# Heaters.net
KiCad netlist of a schematic drawn in Altium Designer
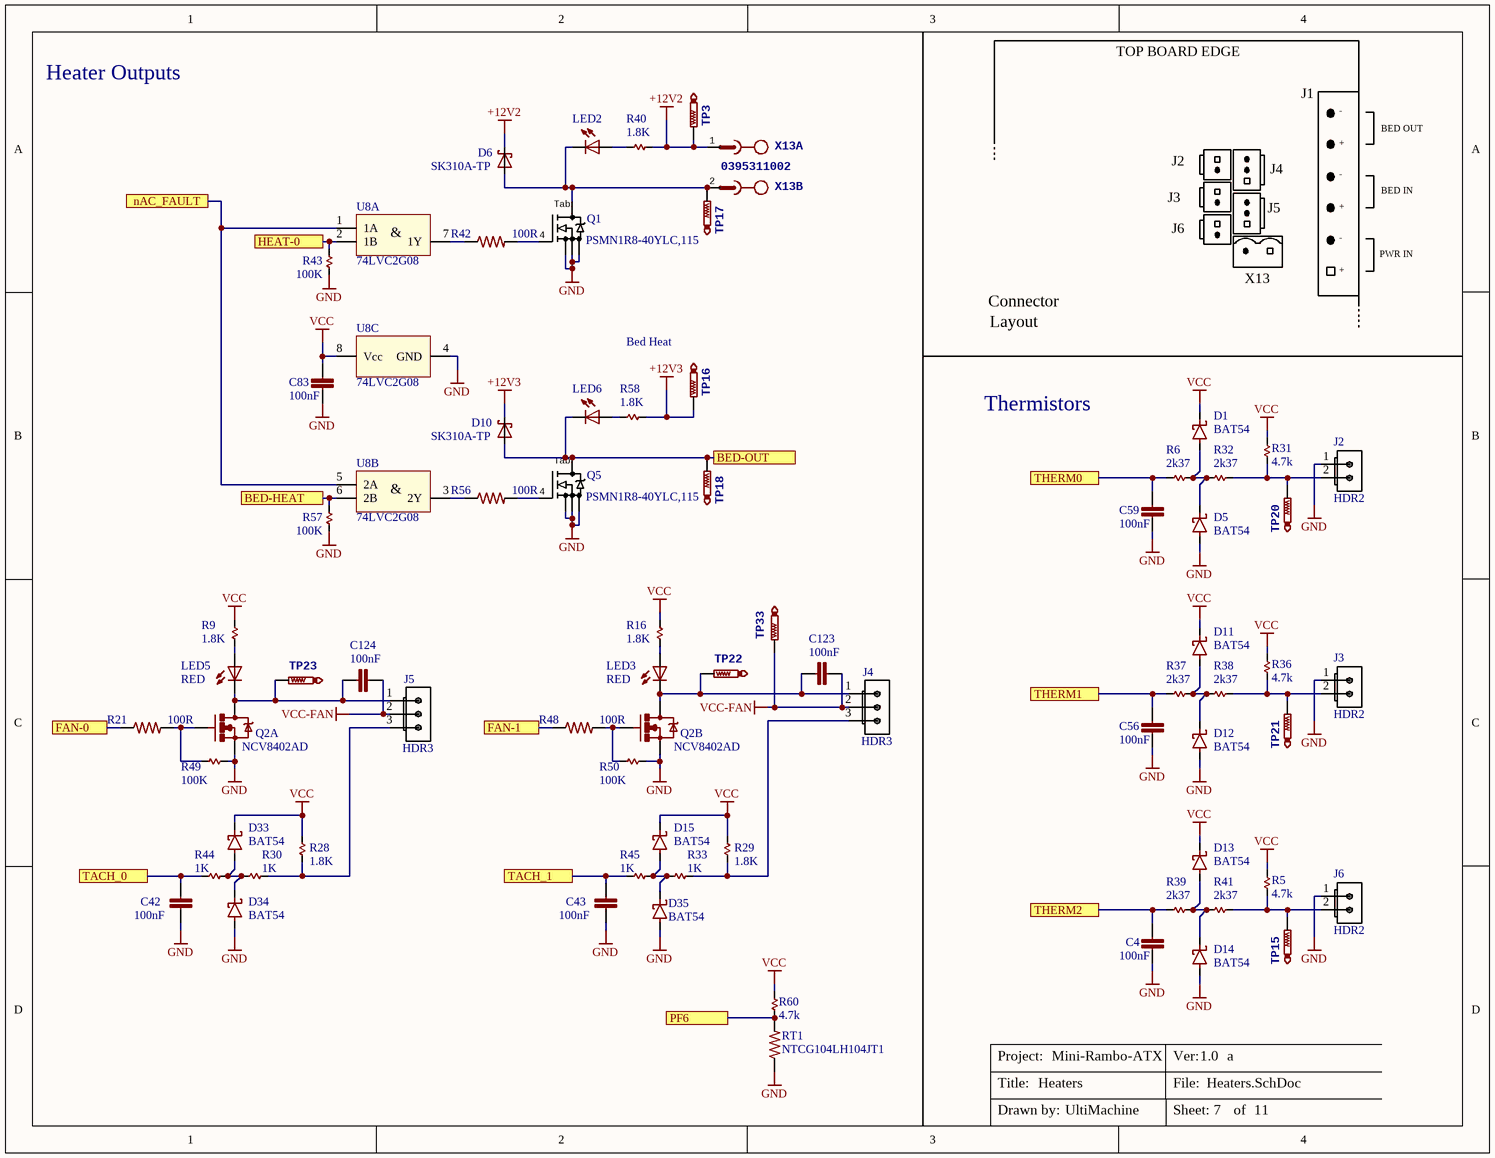
[diagram p0: Heaters.SchDoc]

(export (version "E")
  (design (tool "Eeschema 10.0.6"))
  (components
    (comp (ref "C4")
      (value "100nF")
      (footprint "C0402")
      (description "CAP CER 0402 100nF 16V 10% X7R")
      (fields (field (name "MANUFACTURER") "Murata") (field (name "TOLERANCE") "+/- 10%"))
      (libsource (lib "3Delight") (part "GRM155R71C104KA88D"))
    )
    (comp (ref "C42")
      (value "100nF")
      (footprint "C0402")
      (description "CAP CER 0402 100nF 16V 10% X7R")
      (fields (field (name "MANUFACTURER") "Murata") (field (name "TOLERANCE") "+/- 10%"))
      (libsource (lib "3Delight") (part "GRM155R71C104KA88D"))
    )
    (comp (ref "C43")
      (value "100nF")
      (footprint "C0402")
      (description "CAP CER 0402 100nF 16V 10% X7R")
      (fields (field (name "MANUFACTURER") "Murata") (field (name "TOLERANCE") "+/- 10%"))
      (libsource (lib "3Delight") (part "GRM155R71C104KA88D"))
    )
    (comp (ref "C56")
      (value "100nF")
      (footprint "C0402")
      (description "CAP CER 0402 100nF 16V 10% X7R")
      (fields (field (name "MANUFACTURER") "Murata") (field (name "TOLERANCE") "+/- 10%"))
      (libsource (lib "3Delight") (part "GRM155R71C104KA88D"))
    )
    (comp (ref "C59")
      (value "100nF")
      (footprint "C0402")
      (description "CAP CER 0402 100nF 16V 10% X7R")
      (fields (field (name "MANUFACTURER") "Murata") (field (name "TOLERANCE") "+/- 10%"))
      (libsource (lib "3Delight") (part "GRM155R71C104KA88D"))
    )
    (comp (ref "C83")
      (value "100nF")
      (footprint "C0402")
      (description "CAP CER 0402 100nF 16V 10% X7R")
      (fields (field (name "MANUFACTURER") "Murata") (field (name "TOLERANCE") "+/- 10%"))
      (libsource (lib "3Delight") (part "GRM155R71C104KA88D"))
    )
    (comp (ref "C123")
      (value "100nF")
      (footprint "C0402")
      (description "CAP CER 0402 100nF 16V 10% X7R")
      (fields (field (name "MANUFACTURER") "Murata") (field (name "TOLERANCE") "+/- 10%"))
      (libsource (lib "") (part "GRM155R71C104KA88D_1"))
    )
    (comp (ref "C124")
      (value "100nF")
      (footprint "C0402")
      (description "CAP CER 0402 100nF 16V 10% X7R")
      (fields (field (name "MANUFACTURER") "Murata") (field (name "TOLERANCE") "+/- 10%"))
      (libsource (lib "") (part "GRM155R71C104KA88D_1"))
    )
    (comp (ref "D1")
      (value "BAT54")
      (footprint "SOD523_IPC")
      (description "Diode Schottky 30V 100mA Surface Mount SOD-523")
      (fields (field (name "MANUFACTURER") "Diodes Incorporated") (field (name "TOLERANCE") "NA"))
      (libsource (lib "3Delight") (part "BAT54WT-7"))
    )
    (comp (ref "D5")
      (value "BAT54")
      (footprint "SOD523_IPC")
      (description "Diode Schottky 30V 100mA Surface Mount SOD-523")
      (fields (field (name "MANUFACTURER") "Diodes Incorporated") (field (name "TOLERANCE") "NA"))
      (libsource (lib "3Delight") (part "BAT54WT-7"))
    )
    (comp (ref "D6")
      (value "SK310A-TP")
      (footprint "SMA-SM")
      (description "DIODE Schottky 3A SMA")
      (fields (field (name "MANUFACTURER") "MCC") (field (name "PART") "SK310A"))
      (libsource (lib "3Delight") (part "SK310A"))
    )
    (comp (ref "D10")
      (value "SK310A-TP")
      (footprint "SMA-SM")
      (description "DIODE Schottky 3A SMA")
      (fields (field (name "MANUFACTURER") "MCC") (field (name "PART") "SK310A"))
      (libsource (lib "3Delight") (part "SK310A"))
    )
    (comp (ref "D11")
      (value "BAT54")
      (footprint "SOD523_IPC")
      (description "Diode Schottky 30V 100mA Surface Mount SOD-523")
      (fields (field (name "MANUFACTURER") "Diodes Incorporated") (field (name "TOLERANCE") "NA"))
      (libsource (lib "3Delight") (part "BAT54WT-7"))
    )
    (comp (ref "D12")
      (value "BAT54")
      (footprint "SOD523_IPC")
      (description "Diode Schottky 30V 100mA Surface Mount SOD-523")
      (fields (field (name "MANUFACTURER") "Diodes Incorporated") (field (name "TOLERANCE") "NA"))
      (libsource (lib "3Delight") (part "BAT54WT-7"))
    )
    (comp (ref "D13")
      (value "BAT54")
      (footprint "SOD523_IPC")
      (description "Diode Schottky 30V 100mA Surface Mount SOD-523")
      (fields (field (name "MANUFACTURER") "Diodes Incorporated") (field (name "TOLERANCE") "NA"))
      (libsource (lib "3Delight") (part "BAT54WT-7"))
    )
    (comp (ref "D14")
      (value "BAT54")
      (footprint "SOD523_IPC")
      (description "Diode Schottky 30V 100mA Surface Mount SOD-523")
      (fields (field (name "MANUFACTURER") "Diodes Incorporated") (field (name "TOLERANCE") "NA"))
      (libsource (lib "3Delight") (part "BAT54WT-7"))
    )
    (comp (ref "D15")
      (value "BAT54")
      (footprint "SOD523_IPC")
      (description "Diode Schottky 30V 100mA Surface Mount SOD-523")
      (fields (field (name "MANUFACTURER") "Diodes Incorporated") (field (name "TOLERANCE") "NA"))
      (libsource (lib "3Delight") (part "BAT54WT-7"))
    )
    (comp (ref "D33")
      (value "BAT54")
      (footprint "SOD523_IPC")
      (description "Diode Schottky 30V 100mA Surface Mount SOD-523")
      (fields (field (name "MANUFACTURER") "Diodes Incorporated") (field (name "TOLERANCE") "NA"))
      (libsource (lib "3Delight") (part "BAT54WT-7"))
    )
    (comp (ref "D34")
      (value "BAT54")
      (footprint "SOD523_IPC")
      (description "Diode Schottky 30V 100mA Surface Mount SOD-523")
      (fields (field (name "MANUFACTURER") "Diodes Incorporated") (field (name "TOLERANCE") "NA"))
      (libsource (lib "3Delight") (part "BAT54WT-7"))
    )
    (comp (ref "D35")
      (value "BAT54")
      (footprint "SOD523_IPC")
      (description "Diode Schottky 30V 100mA Surface Mount SOD-523")
      (fields (field (name "MANUFACTURER") "Diodes Incorporated") (field (name "TOLERANCE") "NA"))
      (libsource (lib "3Delight") (part "BAT54WT-7"))
    )
    (comp (ref "J2")
      (value "HDR2")
      (footprint "70543-02 PIN-IN-PASTE")
      (description "Connector 2pos")
      (fields (field (name "MANUFACTURER") "Molex") (field (name "PART") "2 Pin Conn"))
      (libsource (lib "Connectors") (part "CONN 2PIN VERT 0.1{dblquote} SHRD LOCKING PIN-IN-PASTE"))
    )
    (comp (ref "J3")
      (value "HDR2")
      (footprint "70543-02 PIN-IN-PASTE")
      (description "Connector 2pos")
      (fields (field (name "MANUFACTURER") "Molex") (field (name "PART") "2 Pin Conn"))
      (libsource (lib "Connectors") (part "CONN 2PIN VERT 0.1{dblquote} SHRD LOCKING PIN-IN-PASTE"))
    )
    (comp (ref "J4")
      (value "HDR3")
      (footprint "70543-03 PIN-IN-PASTE")
      (description "3 Positions Header, Shrouded Connector 0.100\" (2.54mm) Through Hole Gold")
      (fields (field (name "MANUFACTURER") "Molex") (field (name "PART") "3 Pin Conn VERT"))
      (libsource (lib "Connectors") (part "CONN 3POS VERT 0.1{dblquote} SHRD LOCKING PIN-IN-PASTE"))
    )
    (comp (ref "J5")
      (value "HDR3")
      (footprint "70543-03 PIN-IN-PASTE")
      (description "3 Positions Header, Shrouded Connector 0.100\" (2.54mm) Through Hole Gold")
      (fields (field (name "MANUFACTURER") "Molex") (field (name "PART") "3 Pin Conn VERT"))
      (libsource (lib "Connectors") (part "CONN 3POS VERT 0.1{dblquote} SHRD LOCKING PIN-IN-PASTE"))
    )
    (comp (ref "J6")
      (value "HDR2")
      (footprint "70543-02 PIN-IN-PASTE")
      (description "Connector 2pos")
      (fields (field (name "MANUFACTURER") "Molex") (field (name "PART") "2 Pin Conn"))
      (libsource (lib "Connectors") (part "CONN 2PIN VERT 0.1{dblquote} SHRD LOCKING PIN-IN-PASTE"))
    )
    (comp (ref "LED2")
      (value "RED")
      (footprint "LED2012120")
      (description "LED 0805 Red")
      (fields (field (name "MANUFACTURER") "Dialight") (field (name "TOLERANCE") "NA"))
      (libsource (lib "3Delight") (part "5988110107F"))
    )
    (comp (ref "LED3")
      (value "RED")
      (footprint "LED2012120")
      (description "LED 0805 Red")
      (fields
        (field (name "MANUFACTURER") "Dialight")
        (field (name "PART") "RED")
        (field (name "TOLERANCE") "NA")
      )
      (libsource (lib "3Delight") (part "5988110107F"))
    )
    (comp (ref "LED5")
      (value "RED")
      (footprint "LED2012120")
      (description "LED 0805 Red")
      (fields
        (field (name "MANUFACTURER") "Dialight")
        (field (name "PART") "RED")
        (field (name "TOLERANCE") "NA")
      )
      (libsource (lib "3Delight") (part "5988110107F"))
    )
    (comp (ref "LED6")
      (value "RED")
      (footprint "LED2012120")
      (description "LED 0805 Red")
      (fields (field (name "MANUFACTURER") "Dialight") (field (name "TOLERANCE") "NA"))
      (libsource (lib "3Delight") (part "5988110107F"))
    )
    (comp (ref "Q1")
      (value "PSMN1R8-40YLC,115")
      (footprint "SOT669_ClosedBotVias")
      (description "MOSFET N-CH 40V 100A LFPAK")
      (fields (field (name "MANUFACTURER") "Nexperia") (field (name "TOLERANCE") "-NA-"))
      (libsource (lib "Transistors") (part "PSMN1R8-40YLC_ClosedBotVias"))
    )
    (comp (ref "Q2")
      (value "NCV8402AD")
      (footprint "NCV8402AD-SOIC8")
      (description "IC DVR LOW SIDE 8-SOIC")
      (fields (field (name "MANUFACTURER") "On Semi") (field (name "PART") "NCV8402"))
      (libsource (lib "3Delight") (part "NCV8402AD"))
    )
    (comp (ref "Q5")
      (value "PSMN1R8-40YLC,115")
      (footprint "SOT669_ClosedBotVias")
      (description "MOSFET N-CH 40V 100A LFPAK")
      (fields (field (name "MANUFACTURER") "Nexperia") (field (name "TOLERANCE") "-NA-"))
      (libsource (lib "Transistors") (part "PSMN1R8-40YLC_ClosedBotVias"))
    )
    (comp (ref "R5")
      (value "4.7k")
      (footprint "R0402")
      (description "RES SMD 4.7K OHM 1% 1/16W 0402")
      (fields (field (name "MANUFACTURER") "Yageo") (field (name "TOLERANCE") "+/- 1%"))
      (libsource (lib "3Delight") (part "RC0402FR-074K7L"))
    )
    (comp (ref "R6")
      (value "2k37")
      (footprint "R0402")
      (description "RES SMD 2.37K OHM 1% 1/16W 0402")
      (fields (field (name "MANUFACTURER") "Yageo") (field (name "PART") "2.37k"))
      (libsource (lib "3Delight") (part "RC0402FR-072K37L"))
    )
    (comp (ref "R9")
      (value "1.8K")
      (footprint "R0402")
      (description "RES SMD 1.8K OHM 1% 1/16W 0402")
      (fields (field (name "MANUFACTURER") "Yageo") (field (name "PART") "1.8k"))
      (libsource (lib "3Delight") (part "RC0402FR-071K8L"))
    )
    (comp (ref "R16")
      (value "1.8K")
      (footprint "R0402")
      (description "RES SMD 1.8K OHM 1% 1/16W 0402")
      (fields (field (name "MANUFACTURER") "Yageo") (field (name "PART") "1.8k"))
      (libsource (lib "3Delight") (part "RC0402FR-071K8L"))
    )
    (comp (ref "R21")
      (value "100R")
      (footprint "R0402")
      (description "RES SMD 100 OHM 1% 1/16W 0402")
      (fields (field (name "MANUFACTURER") "Yageo") (field (name "PART") "100R 1% 0402"))
      (libsource (lib "Archim") (part "RES 100R 0402 1%"))
    )
    (comp (ref "R28")
      (value "1.8K")
      (footprint "R0402")
      (description "RES SMD 1.8K OHM 1% 1/16W 0402")
      (fields (field (name "MANUFACTURER") "Yageo") (field (name "PART") "1.8k"))
      (libsource (lib "3Delight") (part "RC0402FR-071K8L"))
    )
    (comp (ref "R29")
      (value "1.8K")
      (footprint "R0402")
      (description "RES SMD 1.8K OHM 1% 1/16W 0402")
      (fields (field (name "MANUFACTURER") "Yageo") (field (name "PART") "1.8k"))
      (libsource (lib "3Delight") (part "RC0402FR-071K8L"))
    )
    (comp (ref "R30")
      (value "1K")
      (footprint "R0402")
      (description "RES SMD 1K OHM 1% 1/16W 0402")
      (fields (field (name "MANUFACTURER") "Yageo") (field (name "PART") "1k"))
      (libsource (lib "3Delight") (part "RC0402FR-071KL"))
    )
    (comp (ref "R31")
      (value "4.7k")
      (footprint "R0402")
      (description "RES SMD 4.7K OHM 1% 1/16W 0402")
      (fields (field (name "MANUFACTURER") "Yageo") (field (name "TOLERANCE") "+/- 1%"))
      (libsource (lib "3Delight") (part "RC0402FR-074K7L"))
    )
    (comp (ref "R32")
      (value "2k37")
      (footprint "R0402")
      (description "RES SMD 2.37K OHM 1% 1/16W 0402")
      (fields (field (name "MANUFACTURER") "Yageo") (field (name "PART") "2.37k"))
      (libsource (lib "3Delight") (part "RC0402FR-072K37L"))
    )
    (comp (ref "R33")
      (value "1K")
      (footprint "R0402")
      (description "RES SMD 1K OHM 1% 1/16W 0402")
      (fields (field (name "MANUFACTURER") "Yageo") (field (name "PART") "1k"))
      (libsource (lib "3Delight") (part "RC0402FR-071KL"))
    )
    (comp (ref "R36")
      (value "4.7k")
      (footprint "R0402")
      (description "RES SMD 4.7K OHM 1% 1/16W 0402")
      (fields (field (name "MANUFACTURER") "Yageo") (field (name "TOLERANCE") "+/- 1%"))
      (libsource (lib "3Delight") (part "RC0402FR-074K7L"))
    )
    (comp (ref "R37")
      (value "2k37")
      (footprint "R0402")
      (description "RES SMD 2.37K OHM 1% 1/16W 0402")
      (fields (field (name "MANUFACTURER") "Yageo") (field (name "PART") "2.37k"))
      (libsource (lib "3Delight") (part "RC0402FR-072K37L"))
    )
    (comp (ref "R38")
      (value "2k37")
      (footprint "R0402")
      (description "RES SMD 2.37K OHM 1% 1/16W 0402")
      (fields (field (name "MANUFACTURER") "Yageo") (field (name "PART") "2.37k"))
      (libsource (lib "3Delight") (part "RC0402FR-072K37L"))
    )
    (comp (ref "R39")
      (value "2k37")
      (footprint "R0402")
      (description "RES SMD 2.37K OHM 1% 1/16W 0402")
      (fields (field (name "MANUFACTURER") "Yageo") (field (name "PART") "2.37k"))
      (libsource (lib "3Delight") (part "RC0402FR-072K37L"))
    )
    (comp (ref "R40")
      (value "1.8K")
      (footprint "R0402")
      (description "RES SMD 1.8K OHM 1% 1/16W 0402")
      (fields (field (name "MANUFACTURER") "Yageo") (field (name "PART") "1.8k"))
      (libsource (lib "3Delight") (part "RC0402FR-071K8L"))
    )
    (comp (ref "R41")
      (value "2k37")
      (footprint "R0402")
      (description "RES SMD 2.37K OHM 1% 1/16W 0402")
      (fields (field (name "MANUFACTURER") "Yageo") (field (name "PART") "2.37k"))
      (libsource (lib "3Delight") (part "RC0402FR-072K37L"))
    )
    (comp (ref "R42")
      (value "100R")
      (footprint "R0402")
      (description "RES SMD 100 OHM 1% 1/16W 0402")
      (fields (field (name "MANUFACTURER") "Yageo") (field (name "PART") "100R 1% 0402"))
      (libsource (lib "Archim") (part "RES 100R 0402 1%"))
    )
    (comp (ref "R43")
      (value "100K")
      (footprint "R0402")
      (description "RES 100K OHM 1% 1/16W 0402")
      (fields (field (name "MANUFACTURER") "Yageo") (field (name "TOLERANCE") "+/- 1%"))
      (libsource (lib "3Delight") (part "RC0402FR-07100KL"))
    )
    (comp (ref "R44")
      (value "1K")
      (footprint "R0402")
      (description "RES SMD 1K OHM 1% 1/16W 0402")
      (fields (field (name "MANUFACTURER") "Yageo") (field (name "PART") "1k"))
      (libsource (lib "3Delight") (part "RC0402FR-071KL"))
    )
    (comp (ref "R45")
      (value "1K")
      (footprint "R0402")
      (description "RES SMD 1K OHM 1% 1/16W 0402")
      (fields (field (name "MANUFACTURER") "Yageo") (field (name "PART") "1k"))
      (libsource (lib "3Delight") (part "RC0402FR-071KL"))
    )
    (comp (ref "R48")
      (value "100R")
      (footprint "R0402")
      (description "RES SMD 100 OHM 1% 1/16W 0402")
      (fields (field (name "MANUFACTURER") "Yageo") (field (name "PART") "100R 1% 0402"))
      (libsource (lib "Archim") (part "RES 100R 0402 1%"))
    )
    (comp (ref "R49")
      (value "100K")
      (footprint "R0402")
      (description "RES 100K OHM 1% 1/16W 0402")
      (fields (field (name "MANUFACTURER") "Yageo") (field (name "TOLERANCE") "+/- 1%"))
      (libsource (lib "3Delight") (part "RC0402FR-07100KL"))
    )
    (comp (ref "R50")
      (value "100K")
      (footprint "R0402")
      (description "RES 100K OHM 1% 1/16W 0402")
      (fields (field (name "MANUFACTURER") "Yageo") (field (name "TOLERANCE") "+/- 1%"))
      (libsource (lib "3Delight") (part "RC0402FR-07100KL"))
    )
    (comp (ref "R56")
      (value "100R")
      (footprint "R0402")
      (description "RES SMD 100 OHM 1% 1/16W 0402")
      (fields (field (name "MANUFACTURER") "Yageo") (field (name "PART") "100R 1% 0402"))
      (libsource (lib "Archim") (part "RES 100R 0402 1%"))
    )
    (comp (ref "R57")
      (value "100K")
      (footprint "R0402")
      (description "RES 100K OHM 1% 1/16W 0402")
      (fields (field (name "MANUFACTURER") "Yageo") (field (name "TOLERANCE") "+/- 1%"))
      (libsource (lib "3Delight") (part "RC0402FR-07100KL"))
    )
    (comp (ref "R58")
      (value "1.8K")
      (footprint "R0402")
      (description "RES SMD 1.8K OHM 1% 1/16W 0402")
      (fields (field (name "MANUFACTURER") "Yageo") (field (name "PART") "1.8k"))
      (libsource (lib "3Delight") (part "RC0402FR-071K8L"))
    )
    (comp (ref "R60")
      (value "4.7k")
      (footprint "R0402")
      (description "RES SMD 4.7K OHM 1% 1/16W 0402")
      (fields (field (name "MANUFACTURER") "Yageo") (field (name "TOLERANCE") "+/- 1%"))
      (libsource (lib "3Delight") (part "RC0402FR-074K7L"))
    )
    (comp (ref "RT1")
      (value "NTCG104LH104JT1")
      (footprint "R0402")
      (description "Resistor")
      (fields (field (name "PUBLISHER") "UltiMachine"))
      (libsource (lib "3Delight") (part "R0402TBD"))
    )
    (comp (ref "TP3")
      (value "TestPoint")
      (footprint "TP1-27")
      (description "Test Point")
      (libsource (lib "3Delight") (part "TestPoint"))
    )
    (comp (ref "TP15")
      (value "TestPoint")
      (footprint "TP1-27")
      (description "Test Point")
      (libsource (lib "") (part "TestPoint_1"))
    )
    (comp (ref "TP16")
      (value "TestPoint")
      (footprint "TP1-27")
      (description "Test Point")
      (libsource (lib "3Delight") (part "TestPoint"))
    )
    (comp (ref "TP17")
      (value "TestPoint")
      (footprint "TP1-27")
      (description "Test Point")
      (libsource (lib "") (part "TestPoint_1"))
    )
    (comp (ref "TP18")
      (value "TestPoint")
      (footprint "TP1-27")
      (description "Test Point")
      (libsource (lib "") (part "TestPoint_1"))
    )
    (comp (ref "TP20")
      (value "TestPoint")
      (footprint "TP1-27")
      (description "Test Point")
      (libsource (lib "") (part "TestPoint_1"))
    )
    (comp (ref "TP21")
      (value "TestPoint")
      (footprint "TP1-27")
      (description "Test Point")
      (libsource (lib "") (part "TestPoint_1"))
    )
    (comp (ref "TP22")
      (value "TestPoint")
      (footprint "TP1-27")
      (description "Test Point")
      (libsource (lib "") (part "TestPoint_2"))
    )
    (comp (ref "TP23")
      (value "TestPoint")
      (footprint "TP1-27")
      (description "Test Point")
      (libsource (lib "") (part "TestPoint_2"))
    )
    (comp (ref "TP33")
      (value "TestPoint")
      (footprint "TP1-27")
      (description "Test Point")
      (libsource (lib "3Delight") (part "TestPoint"))
    )
    (comp (ref "U8")
      (value "74LVC2G08")
      (footprint "VSSOP8")
      (description "IC GATE AND 2CH 2-INP 8-VSSOP")
      (fields (field (name "TOLERANCE") "-NA-") (field (name "MANUFACTURER") "Nexperia"))
      (libsource (lib "ICs-Logic") (part "74LVC2G08"))
    )
    (comp (ref "X13")
      (value "0395311002")
      (footprint "MSTBV2")
      (description "Conn - 5.08mm Pitch Fixed")
      (fields (field (name "MANUFACTURER") "Molex") (field (name "PART") "2POS"))
      (libsource (lib "") (part "0395311002_1"))
    )
  )
  (nets
    (net (code "1") (name "+12V2") (class "Default")
      (node (ref "D6") (pin "C") (pinfunction "C_C") (pintype "passive"))
      (node (ref "R40") (pin "1") (pinfunction "1_1") (pintype "passive"))
      (node (ref "TP3") (pin "TP") (pinfunction "TP_TP") (pintype "passive"))
      (node (ref "X13") (pin "1") (pinfunction "1_1") (pintype "passive"))
    )
    (net (code "2") (name "+12V3") (class "Default")
      (node (ref "D10") (pin "C") (pinfunction "C_C") (pintype "passive"))
      (node (ref "R58") (pin "1") (pinfunction "1_1") (pintype "passive"))
      (node (ref "TP16") (pin "TP") (pinfunction "TP_TP") (pintype "passive"))
    )
    (net (code "3") (name "/BED-HEAT") (class "Default")
      (node (ref "R57") (pin "2") (pinfunction "2_2") (pintype "passive"))
      (node (ref "U8") (pin "6") (pinfunction "2B_6") (pintype "passive"))
    )
    (net (code "4") (name "/BED-OUT") (class "Default")
      (node (ref "D10") (pin "A") (pinfunction "A_A") (pintype "passive"))
      (node (ref "LED6") (pin "C") (pinfunction "C_C") (pintype "passive"))
      (node (ref "Q5") (pin "TAB") (pinfunction "D_TAB") (pintype "passive"))
      (node (ref "TP18") (pin "TP") (pinfunction "TP_TP") (pintype "passive"))
    )
    (net (code "5") (name "/FAN-0") (class "Default")
      (node (ref "R21") (pin "1") (pinfunction "1_1") (pintype "passive"))
    )
    (net (code "6") (name "/FAN-1") (class "Default")
      (node (ref "R48") (pin "1") (pinfunction "1_1") (pintype "passive"))
    )
    (net (code "7") (name "/HEAT-0") (class "Default")
      (node (ref "R43") (pin "2") (pinfunction "2_2") (pintype "passive"))
      (node (ref "U8") (pin "2") (pinfunction "1B_2") (pintype "passive"))
    )
    (net (code "8") (name "/PF6") (class "Default")
      (node (ref "R60") (pin "1") (pinfunction "1_1") (pintype "passive"))
      (node (ref "RT1") (pin "2") (pinfunction "2_2") (pintype "passive"))
    )
    (net (code "9") (name "/TACH_0") (class "Default")
      (node (ref "C42") (pin "1") (pinfunction "1_1") (pintype "passive"))
      (node (ref "R44") (pin "1") (pinfunction "1_1") (pintype "passive"))
    )
    (net (code "10") (name "/TACH_1") (class "Default")
      (node (ref "C43") (pin "1") (pinfunction "1_1") (pintype "passive"))
      (node (ref "R45") (pin "1") (pinfunction "1_1") (pintype "passive"))
    )
    (net (code "11") (name "/THERM0") (class "Default")
      (node (ref "C59") (pin "1") (pinfunction "1_1") (pintype "passive"))
      (node (ref "R6") (pin "2") (pinfunction "2_2") (pintype "passive"))
    )
    (net (code "12") (name "/THERM1") (class "Default")
      (node (ref "C56") (pin "1") (pinfunction "1_1") (pintype "passive"))
      (node (ref "R37") (pin "2") (pinfunction "2_2") (pintype "passive"))
    )
    (net (code "13") (name "/THERM2") (class "Default")
      (node (ref "C4") (pin "1") (pinfunction "1_1") (pintype "passive"))
      (node (ref "R39") (pin "2") (pinfunction "2_2") (pintype "passive"))
    )
    (net (code "14") (name "/nAC_FAULT") (class "Default")
      (node (ref "U8") (pin "1") (pinfunction "1A_1") (pintype "passive"))
      (node (ref "U8") (pin "5") (pinfunction "2A_5") (pintype "passive"))
    )
    (net (code "15") (name "GND") (class "Default")
      (node (ref "C4") (pin "2") (pinfunction "2_2") (pintype "passive"))
      (node (ref "C42") (pin "2") (pinfunction "2_2") (pintype "passive"))
      (node (ref "C43") (pin "2") (pinfunction "2_2") (pintype "passive"))
      (node (ref "C56") (pin "2") (pinfunction "2_2") (pintype "passive"))
      (node (ref "C59") (pin "2") (pinfunction "2_2") (pintype "passive"))
      (node (ref "C83") (pin "2") (pinfunction "2_2") (pintype "passive"))
      (node (ref "D12") (pin "A") (pinfunction "A_A") (pintype "passive"))
      (node (ref "D14") (pin "A") (pinfunction "A_A") (pintype "passive"))
      (node (ref "D34") (pin "A") (pinfunction "A_A") (pintype "passive"))
      (node (ref "D35") (pin "A") (pinfunction "A_A") (pintype "passive"))
      (node (ref "D5") (pin "A") (pinfunction "A_A") (pintype "passive"))
      (node (ref "J2") (pin "1") (pinfunction "S_1") (pintype "passive"))
      (node (ref "J3") (pin "1") (pinfunction "S_1") (pintype "passive"))
      (node (ref "J6") (pin "1") (pinfunction "S_1") (pintype "passive"))
      (node (ref "Q1") (pin "1") (pinfunction "S_1") (pintype "passive"))
      (node (ref "Q1") (pin "2") (pinfunction "S_2") (pintype "passive"))
      (node (ref "Q1") (pin "3") (pinfunction "S_3") (pintype "passive"))
      (node (ref "Q2") (pin "1") (pinfunction "S_1") (pintype "passive"))
      (node (ref "Q2") (pin "3") (pinfunction "S_3") (pintype "passive"))
      (node (ref "Q5") (pin "1") (pinfunction "S_1") (pintype "passive"))
      (node (ref "Q5") (pin "2") (pinfunction "S_2") (pintype "passive"))
      (node (ref "Q5") (pin "3") (pinfunction "S_3") (pintype "passive"))
      (node (ref "R43") (pin "1") (pinfunction "1_1") (pintype "passive"))
      (node (ref "R49") (pin "2") (pinfunction "2_2") (pintype "passive"))
      (node (ref "R50") (pin "2") (pinfunction "2_2") (pintype "passive"))
      (node (ref "R57") (pin "1") (pinfunction "1_1") (pintype "passive"))
      (node (ref "RT1") (pin "1") (pinfunction "1_1") (pintype "passive"))
      (node (ref "U8") (pin "4") (pinfunction "GND_4") (pintype "passive"))
    )
    (net (code "16") (name "Net-(D1-PadA)") (class "Default")
      (node (ref "D1") (pin "A") (pinfunction "A_A") (pintype "passive"))
      (node (ref "D5") (pin "K") (pinfunction "K_K") (pintype "passive"))
      (node (ref "R32") (pin "2") (pinfunction "2_2") (pintype "passive"))
      (node (ref "R6") (pin "1") (pinfunction "1_1") (pintype "passive"))
    )
    (net (code "17") (name "Net-(D11-PadA)") (class "Default")
      (node (ref "D11") (pin "A") (pinfunction "A_A") (pintype "passive"))
      (node (ref "D12") (pin "K") (pinfunction "K_K") (pintype "passive"))
      (node (ref "R37") (pin "1") (pinfunction "1_1") (pintype "passive"))
      (node (ref "R38") (pin "2") (pinfunction "2_2") (pintype "passive"))
    )
    (net (code "18") (name "Net-(D13-PadA)") (class "Default")
      (node (ref "D13") (pin "A") (pinfunction "A_A") (pintype "passive"))
      (node (ref "D14") (pin "K") (pinfunction "K_K") (pintype "passive"))
      (node (ref "R39") (pin "1") (pinfunction "1_1") (pintype "passive"))
      (node (ref "R41") (pin "2") (pinfunction "2_2") (pintype "passive"))
    )
    (net (code "19") (name "Net-(D15-PadA)") (class "Default")
      (node (ref "D15") (pin "A") (pinfunction "A_A") (pintype "passive"))
      (node (ref "D35") (pin "K") (pinfunction "K_K") (pintype "passive"))
      (node (ref "R33") (pin "1") (pinfunction "1_1") (pintype "passive"))
      (node (ref "R45") (pin "2") (pinfunction "2_2") (pintype "passive"))
    )
    (net (code "20") (name "Net-(D33-PadA)") (class "Default")
      (node (ref "D33") (pin "A") (pinfunction "A_A") (pintype "passive"))
      (node (ref "D34") (pin "K") (pinfunction "K_K") (pintype "passive"))
      (node (ref "R30") (pin "1") (pinfunction "1_1") (pintype "passive"))
      (node (ref "R44") (pin "2") (pinfunction "2_2") (pintype "passive"))
    )
    (net (code "21") (name "Net-(J2-S-Pad2)") (class "Default")
      (node (ref "J2") (pin "2") (pinfunction "S_2") (pintype "passive"))
      (node (ref "R31") (pin "1") (pinfunction "1_1") (pintype "passive"))
      (node (ref "R32") (pin "1") (pinfunction "1_1") (pintype "passive"))
      (node (ref "TP20") (pin "TP") (pinfunction "TP_TP") (pintype "passive"))
    )
    (net (code "22") (name "Net-(J3-S-Pad2)") (class "Default")
      (node (ref "J3") (pin "2") (pinfunction "S_2") (pintype "passive"))
      (node (ref "R36") (pin "1") (pinfunction "1_1") (pintype "passive"))
      (node (ref "R38") (pin "1") (pinfunction "1_1") (pintype "passive"))
      (node (ref "TP21") (pin "TP") (pinfunction "TP_TP") (pintype "passive"))
    )
    (net (code "23") (name "Net-(J4-S-Pad3)") (class "Default")
      (node (ref "J4") (pin "3") (pinfunction "S_3") (pintype "passive"))
      (node (ref "R29") (pin "1") (pinfunction "1_1") (pintype "passive"))
      (node (ref "R33") (pin "2") (pinfunction "2_2") (pintype "passive"))
    )
    (net (code "24") (name "Net-(J5-S-Pad3)") (class "Default")
      (node (ref "J5") (pin "3") (pinfunction "S_3") (pintype "passive"))
      (node (ref "R28") (pin "1") (pinfunction "1_1") (pintype "passive"))
      (node (ref "R30") (pin "2") (pinfunction "2_2") (pintype "passive"))
    )
    (net (code "25") (name "Net-(J6-S-Pad2)") (class "Default")
      (node (ref "J6") (pin "2") (pinfunction "S_2") (pintype "passive"))
      (node (ref "R41") (pin "1") (pinfunction "1_1") (pintype "passive"))
      (node (ref "R5") (pin "1") (pinfunction "1_1") (pintype "passive"))
      (node (ref "TP15") (pin "TP") (pinfunction "TP_TP") (pintype "passive"))
    )
    (net (code "26") (name "Net-(LED2-PadA)") (class "Default")
      (node (ref "LED2") (pin "A") (pinfunction "A_A") (pintype "passive"))
      (node (ref "R40") (pin "2") (pinfunction "2_2") (pintype "passive"))
    )
    (net (code "27") (name "Net-(LED3-PadA)") (class "Default")
      (node (ref "LED3") (pin "A") (pinfunction "A_A") (pintype "passive"))
      (node (ref "R16") (pin "2") (pinfunction "2_2") (pintype "passive"))
    )
    (net (code "28") (name "Net-(LED5-PadA)") (class "Default")
      (node (ref "LED5") (pin "A") (pinfunction "A_A") (pintype "passive"))
      (node (ref "R9") (pin "2") (pinfunction "2_2") (pintype "passive"))
    )
    (net (code "29") (name "Net-(LED6-PadA)") (class "Default")
      (node (ref "LED6") (pin "A") (pinfunction "A_A") (pintype "passive"))
      (node (ref "R58") (pin "2") (pinfunction "2_2") (pintype "passive"))
    )
    (net (code "30") (name "Net-(Q1-D)") (class "Default")
      (node (ref "D6") (pin "A") (pinfunction "A_A") (pintype "passive"))
      (node (ref "LED2") (pin "C") (pinfunction "C_C") (pintype "passive"))
      (node (ref "Q1") (pin "TAB") (pinfunction "D_TAB") (pintype "passive"))
      (node (ref "TP17") (pin "TP") (pinfunction "TP_TP") (pintype "passive"))
      (node (ref "X13") (pin "2") (pinfunction "1_2") (pintype "passive"))
    )
    (net (code "31") (name "Net-(Q1-G)") (class "Default")
      (node (ref "Q1") (pin "4") (pinfunction "G_4") (pintype "passive"))
      (node (ref "R42") (pin "2") (pinfunction "2_2") (pintype "passive"))
    )
    (net (code "32") (name "Net-(Q2A-D)") (class "Default")
      (node (ref "C124") (pin "1") (pinfunction "1_1") (pintype "passive"))
      (node (ref "J5") (pin "1") (pinfunction "S_1") (pintype "passive"))
      (node (ref "LED5") (pin "C") (pinfunction "C_C") (pintype "passive"))
      (node (ref "Q2") (pin "7") (pinfunction "D_7") (pintype "passive"))
      (node (ref "TP23") (pin "TP") (pinfunction "TP_TP") (pintype "passive"))
    )
    (net (code "33") (name "Net-(Q2A-G)") (class "Default")
      (node (ref "Q2") (pin "2") (pinfunction "G_2") (pintype "passive"))
      (node (ref "R21") (pin "2") (pinfunction "2_2") (pintype "passive"))
      (node (ref "R49") (pin "1") (pinfunction "1_1") (pintype "passive"))
    )
    (net (code "34") (name "Net-(Q2B-D)") (class "Default")
      (node (ref "C123") (pin "1") (pinfunction "1_1") (pintype "passive"))
      (node (ref "J4") (pin "1") (pinfunction "S_1") (pintype "passive"))
      (node (ref "LED3") (pin "C") (pinfunction "C_C") (pintype "passive"))
      (node (ref "Q2") (pin "5") (pinfunction "D_5") (pintype "passive"))
      (node (ref "TP22") (pin "TP") (pinfunction "TP_TP") (pintype "passive"))
    )
    (net (code "35") (name "Net-(Q2B-G)") (class "Default")
      (node (ref "Q2") (pin "4") (pinfunction "G_4") (pintype "passive"))
      (node (ref "R48") (pin "2") (pinfunction "2_2") (pintype "passive"))
      (node (ref "R50") (pin "1") (pinfunction "1_1") (pintype "passive"))
    )
    (net (code "36") (name "Net-(Q5-G)") (class "Default")
      (node (ref "Q5") (pin "4") (pinfunction "G_4") (pintype "passive"))
      (node (ref "R56") (pin "2") (pinfunction "2_2") (pintype "passive"))
    )
    (net (code "37") (name "Net-(U8A-1Y)") (class "Default")
      (node (ref "R42") (pin "1") (pinfunction "1_1") (pintype "passive"))
      (node (ref "U8") (pin "7") (pinfunction "1Y_7") (pintype "passive"))
    )
    (net (code "38") (name "Net-(U8B-2Y)") (class "Default")
      (node (ref "R56") (pin "1") (pinfunction "1_1") (pintype "passive"))
      (node (ref "U8") (pin "3") (pinfunction "2Y_3") (pintype "passive"))
    )
    (net (code "39") (name "VCC") (class "Default")
      (node (ref "C83") (pin "1") (pinfunction "1_1") (pintype "passive"))
      (node (ref "D1") (pin "K") (pinfunction "K_K") (pintype "passive"))
      (node (ref "D11") (pin "K") (pinfunction "K_K") (pintype "passive"))
      (node (ref "D13") (pin "K") (pinfunction "K_K") (pintype "passive"))
      (node (ref "D15") (pin "K") (pinfunction "K_K") (pintype "passive"))
      (node (ref "D33") (pin "K") (pinfunction "K_K") (pintype "passive"))
      (node (ref "R16") (pin "1") (pinfunction "1_1") (pintype "passive"))
      (node (ref "R28") (pin "2") (pinfunction "2_2") (pintype "passive"))
      (node (ref "R29") (pin "2") (pinfunction "2_2") (pintype "passive"))
      (node (ref "R31") (pin "2") (pinfunction "2_2") (pintype "passive"))
      (node (ref "R36") (pin "2") (pinfunction "2_2") (pintype "passive"))
      (node (ref "R5") (pin "2") (pinfunction "2_2") (pintype "passive"))
      (node (ref "R60") (pin "2") (pinfunction "2_2") (pintype "passive"))
      (node (ref "R9") (pin "1") (pinfunction "1_1") (pintype "passive"))
      (node (ref "U8") (pin "8") (pinfunction "Vcc_8") (pintype "passive"))
    )
    (net (code "40") (name "VCC-FAN") (class "Default")
      (node (ref "C123") (pin "2") (pinfunction "2_2") (pintype "passive"))
      (node (ref "C124") (pin "2") (pinfunction "2_2") (pintype "passive"))
      (node (ref "J4") (pin "2") (pinfunction "S_2") (pintype "passive"))
      (node (ref "J5") (pin "2") (pinfunction "S_2") (pintype "passive"))
      (node (ref "TP33") (pin "TP") (pinfunction "TP_TP") (pintype "passive"))
    )
    (net (code "41") (name "unconnected-(U8A-NC-Pad23)") (class "Default")
      (node (ref "U8") (pin "23") (pinfunction "NC_23") (pintype "passive"))
    )
  )
)
